# esp8266_relay.net
KiCad netlist of a schematic drawn in Altium Designer
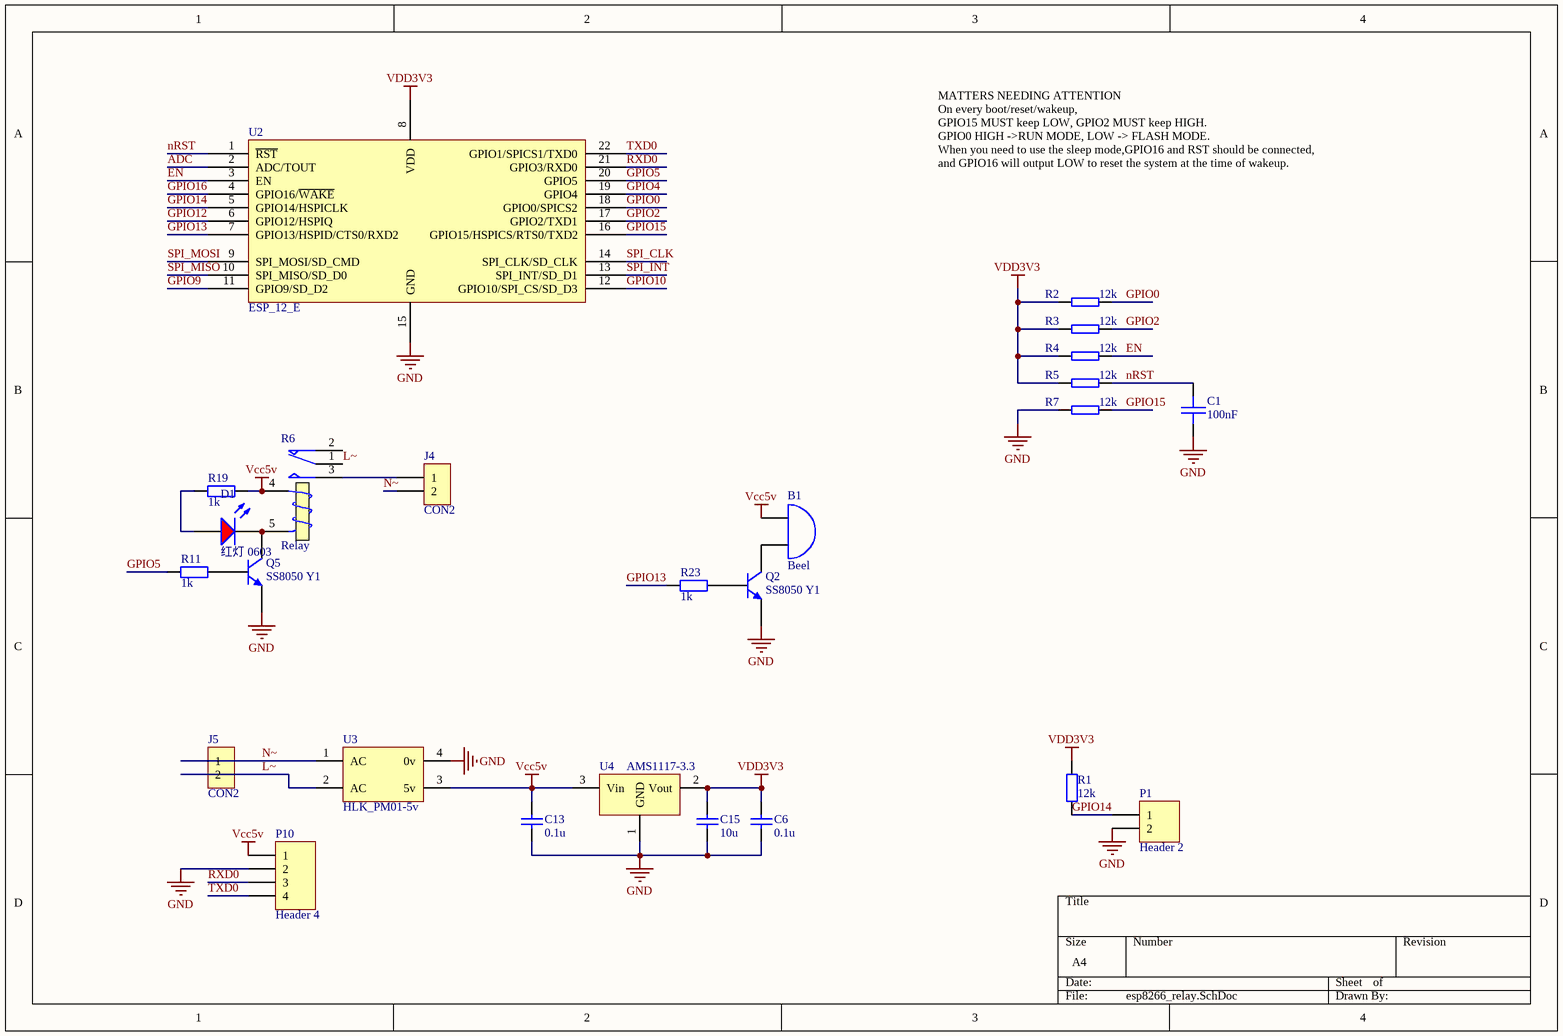
[diagram p0: esp8266_relay.SchDoc]

(export (version "E")
  (design (tool "Eeschema 10.0.6"))
  (components
    (comp (ref "B1") (value "Beel") (footprint "BEEL") (libsource (lib "元件库") (part "Beel")))
    (comp (ref "C1")
      (value "100nF")
      (footprint "C0603")
      (description "Surface mount capacitor 0402")
      (libsource (lib "Vowstar_Basic_Device") (part "SMT_C_0402"))
    )
    (comp (ref "C6") (value "0.1u") (footprint "C0603") (libsource (lib "元件库") (part "Cap_0402")))
    (comp (ref "C13") (value "0.1u") (footprint "C0603") (libsource (lib "元件库") (part "Cap_0402")))
    (comp (ref "C15") (value "10u") (footprint "C0603") (libsource (lib "元件库") (part "Cap_0402")))
    (comp (ref "D1")
      (value "红灯 0603")
      (footprint "0603_LED_S1")
      (description "发光二极管")
      (libsource (lib "Miscellaneous Devices LC") (part "0603 红灯"))
    )
    (comp (ref "J4")
      (value "CON2")
      (footprint "CON_5.08_2")
      (description "Connector")
      (libsource (lib "Miscellaneous Devices") (part "CON2"))
    )
    (comp (ref "J5")
      (value "CON2")
      (footprint "CON_5.08_2")
      (description "Connector")
      (libsource (lib "Miscellaneous Devices") (part "CON2"))
    )
    (comp (ref "P1")
      (value "Header 2")
      (footprint "HDR1X2")
      (description "Header, 2-Pin")
      (fields (field (name "PUBLISHER") "Altium Limited"))
      (libsource (lib "Miscellaneous Connectors") (part "Header 2"))
    )
    (comp (ref "P10")
      (value "Header 4")
      (footprint "HDR1X4")
      (description "Header, 4-Pin")
      (fields (field (name "PUBLISHER") "Altium Limited"))
      (libsource (lib "Miscellaneous Connectors") (part "Header 4"))
    )
    (comp (ref "Q2")
      (value "SS8050 Y1")
      (footprint "SOT-23(SOT-23-3)")
      (description "三极管")
      (libsource (lib "Miscellaneous Devices LC") (part "SOT-23 SS8050 Y1"))
    )
    (comp (ref "Q5")
      (value "SS8050 Y1")
      (footprint "SOT-23(SOT-23-3)")
      (description "三极管")
      (libsource (lib "Miscellaneous Devices LC") (part "SOT-23 SS8050 Y1"))
    )
    (comp (ref "R1") (value "12k") (footprint "Res_0603") (libsource (lib "元件库") (part "Res_0603")))
    (comp (ref "R2")
      (value "12k")
      (footprint "R0603")
      (description "Surface mount resistor 0402")
      (libsource (lib "Vowstar_Basic_Device") (part "SMT_R_0402"))
    )
    (comp (ref "R3")
      (value "12k")
      (footprint "R0603")
      (description "Surface mount resistor 0402")
      (libsource (lib "Vowstar_Basic_Device") (part "SMT_R_0402"))
    )
    (comp (ref "R4")
      (value "12k")
      (footprint "R0603")
      (description "Surface mount resistor 0402")
      (libsource (lib "Vowstar_Basic_Device") (part "SMT_R_0402"))
    )
    (comp (ref "R5")
      (value "12k")
      (footprint "R0603")
      (description "Surface mount resistor 0402")
      (libsource (lib "Vowstar_Basic_Device") (part "SMT_R_0402"))
    )
    (comp (ref "R6") (value "Relay") (footprint "HF3FF-JQC-3FF-005") (libsource (lib "元件库") (part "Relay")))
    (comp (ref "R7")
      (value "12k")
      (footprint "R0603")
      (description "Surface mount resistor 0402")
      (libsource (lib "Vowstar_Basic_Device") (part "SMT_R_0402"))
    )
    (comp (ref "R11") (value "1k") (footprint "R0603") (libsource (lib "元件库") (part "Res_0402")))
    (comp (ref "R19") (value "1k") (footprint "R0603") (libsource (lib "元件库") (part "Res_0402")))
    (comp (ref "R23") (value "1k") (footprint "R0603") (libsource (lib "") (part "Res_0402_1")))
    (comp (ref "U2")
      (value "ESP_12_E")
      (footprint "ESP8266")
      (description "ESP-12 Wi-Fi Module by AI-Thinker")
      (libsource (lib "Vowstar_Module") (part "ESP_12_E"))
    )
    (comp (ref "U3")
      (value "HLK_PM01-5v")
      (footprint "HLK_PM01-5v")
      (libsource (lib "mySchlib") (part "HLK_PM01-5v"))
    )
    (comp (ref "U4") (value "AMS1117-3.3") (footprint "AMS1117") (libsource (lib "元件库") (part "AMS1117")))
  )
  (nets
    (net (code "1") (name "/ADC") (class "Default")
      (node (ref "U2") (pin "2") (pinfunction "ADC/TOUT_2") (pintype "passive"))
    )
    (net (code "2") (name "/EN") (class "Default")
      (node (ref "R4") (pin "2") (pinfunction "2_2") (pintype "passive"))
      (node (ref "U2") (pin "3") (pinfunction "EN_3") (pintype "passive"))
    )
    (net (code "3") (name "/GPIO0") (class "Default")
      (node (ref "R2") (pin "2") (pinfunction "2_2") (pintype "passive"))
      (node (ref "U2") (pin "18") (pinfunction "GPIO0/SPICS2_18") (pintype "passive"))
    )
    (net (code "4") (name "/GPIO2") (class "Default")
      (node (ref "R3") (pin "2") (pinfunction "2_2") (pintype "passive"))
      (node (ref "U2") (pin "17") (pinfunction "GPIO2/TXD1_17") (pintype "passive"))
    )
    (net (code "5") (name "/GPIO4") (class "Default")
      (node (ref "U2") (pin "19") (pinfunction "GPIO4_19") (pintype "passive"))
    )
    (net (code "6") (name "/GPIO5") (class "Default")
      (node (ref "R11") (pin "1") (pinfunction "1_1") (pintype "passive"))
      (node (ref "U2") (pin "20") (pinfunction "GPIO5_20") (pintype "passive"))
    )
    (net (code "7") (name "/GPIO9") (class "Default")
      (node (ref "U2") (pin "11") (pinfunction "GPIO9/SD_D2_11") (pintype "passive"))
    )
    (net (code "8") (name "/GPIO10") (class "Default")
      (node (ref "U2") (pin "12") (pinfunction "GPIO10/SPI_CS/SD_D3_12") (pintype "passive"))
    )
    (net (code "9") (name "/GPIO12") (class "Default")
      (node (ref "U2") (pin "6") (pinfunction "GPIO12/HSPIQ_6") (pintype "passive"))
    )
    (net (code "10") (name "/GPIO13") (class "Default")
      (node (ref "R23") (pin "2") (pinfunction "2_2") (pintype "passive"))
      (node (ref "U2") (pin "7") (pinfunction "GPIO13/HSPID/CTS0/RXD2_7") (pintype "passive"))
    )
    (net (code "11") (name "/GPIO14") (class "Default")
      (node (ref "P1") (pin "1") (pinfunction "1_1") (pintype "passive"))
      (node (ref "R1") (pin "1") (pinfunction "1_1") (pintype "passive"))
      (node (ref "U2") (pin "5") (pinfunction "GPIO14/HSPICLK_5") (pintype "passive"))
    )
    (net (code "12") (name "/GPIO15") (class "Default")
      (node (ref "R7") (pin "2") (pinfunction "2_2") (pintype "passive"))
      (node (ref "U2") (pin "16") (pinfunction "GPIO15/HSPICS/RTS0/TXD2_16") (pintype "passive"))
    )
    (net (code "13") (name "/GPIO16") (class "Default")
      (node (ref "U2") (pin "4") (pinfunction "GPIO16/~{WAKE}_4") (pintype "passive"))
    )
    (net (code "14") (name "/L~") (class "Default")
      (node (ref "J5") (pin "2") (pinfunction "2_2") (pintype "passive"))
      (node (ref "R6") (pin "1") (pinfunction "COM_1") (pintype "passive"))
      (node (ref "U3") (pin "2") (pinfunction "AC_2") (pintype "passive"))
    )
    (net (code "15") (name "/N~") (class "Default")
      (node (ref "J4") (pin "2") (pinfunction "2_2") (pintype "passive"))
      (node (ref "J5") (pin "1") (pinfunction "1_1") (pintype "passive"))
      (node (ref "U3") (pin "1") (pinfunction "AC_1") (pintype "passive"))
    )
    (net (code "16") (name "/RXD0") (class "Default")
      (node (ref "P10") (pin "3") (pinfunction "3_3") (pintype "passive"))
      (node (ref "U2") (pin "21") (pinfunction "GPIO3/RXD0_21") (pintype "passive"))
    )
    (net (code "17") (name "/SPI_CLK") (class "Default")
      (node (ref "U2") (pin "14") (pinfunction "SPI_CLK/SD_CLK_14") (pintype "passive"))
    )
    (net (code "18") (name "/SPI_INT") (class "Default")
      (node (ref "U2") (pin "13") (pinfunction "SPI_INT/SD_D1_13") (pintype "passive"))
    )
    (net (code "19") (name "/SPI_MISO") (class "Default")
      (node (ref "U2") (pin "10") (pinfunction "SPI_MISO/SD_D0_10") (pintype "passive"))
    )
    (net (code "20") (name "/SPI_MOSI") (class "Default")
      (node (ref "U2") (pin "9") (pinfunction "SPI_MOSI/SD_CMD_9") (pintype "passive"))
    )
    (net (code "21") (name "/TXD0") (class "Default")
      (node (ref "P10") (pin "4") (pinfunction "4_4") (pintype "passive"))
      (node (ref "U2") (pin "22") (pinfunction "GPIO1/SPICS1/TXD0_22") (pintype "passive"))
    )
    (net (code "22") (name "/nRST") (class "Default")
      (node (ref "C1") (pin "1") (pinfunction "1_1") (pintype "passive"))
      (node (ref "R5") (pin "2") (pinfunction "2_2") (pintype "passive"))
      (node (ref "U2") (pin "1") (pinfunction "~{RST}_1") (pintype "passive"))
    )
    (net (code "23") (name "GND") (class "Default")
      (node (ref "C1") (pin "2") (pinfunction "2_2") (pintype "passive"))
      (node (ref "C13") (pin "1") (pinfunction "1_1") (pintype "passive"))
      (node (ref "C15") (pin "1") (pinfunction "1_1") (pintype "passive"))
      (node (ref "C6") (pin "1") (pinfunction "1_1") (pintype "passive"))
      (node (ref "P1") (pin "2") (pinfunction "2_2") (pintype "passive"))
      (node (ref "P10") (pin "2") (pinfunction "2_2") (pintype "passive"))
      (node (ref "Q2") (pin "2") (pinfunction "E_2") (pintype "passive"))
      (node (ref "Q5") (pin "2") (pinfunction "E_2") (pintype "passive"))
      (node (ref "R7") (pin "1") (pinfunction "1_1") (pintype "passive"))
      (node (ref "U2") (pin "15") (pinfunction "GND_15") (pintype "passive"))
      (node (ref "U3") (pin "4") (pinfunction "0v_4") (pintype "passive"))
      (node (ref "U4") (pin "1") (pinfunction "GND_1") (pintype "passive"))
    )
    (net (code "24") (name "Net-(B1-B)") (class "Default")
      (node (ref "B1") (pin "2") (pinfunction "B_2") (pintype "passive"))
      (node (ref "Q2") (pin "3") (pinfunction "C_3") (pintype "passive"))
    )
    (net (code "25") (name "Net-(D1-PadA)") (class "Default")
      (node (ref "D1") (pin "A") (pinfunction "A_A") (pintype "passive"))
      (node (ref "R19") (pin "1") (pinfunction "1_1") (pintype "passive"))
    )
    (net (code "26") (name "Net-(Q2-B)") (class "Default")
      (node (ref "Q2") (pin "1") (pinfunction "B_1") (pintype "passive"))
      (node (ref "R23") (pin "1") (pinfunction "1_1") (pintype "passive"))
    )
    (net (code "27") (name "Net-(Q5-B)") (class "Default")
      (node (ref "Q5") (pin "1") (pinfunction "B_1") (pintype "passive"))
      (node (ref "R11") (pin "2") (pinfunction "2_2") (pintype "passive"))
    )
    (net (code "28") (name "Net-(Q5-C)") (class "Default")
      (node (ref "D1") (pin "K") (pinfunction "K_K") (pintype "passive"))
      (node (ref "Q5") (pin "3") (pinfunction "C_3") (pintype "passive"))
      (node (ref "R6") (pin "5") (pinfunction "T2_5") (pintype "passive"))
    )
    (net (code "29") (name "Net-(R6-NO)") (class "Default")
      (node (ref "J4") (pin "1") (pinfunction "1_1") (pintype "passive"))
      (node (ref "R6") (pin "3") (pinfunction "NO_3") (pintype "passive"))
    )
    (net (code "30") (name "VDD3V3") (class "Default")
      (node (ref "C15") (pin "2") (pinfunction "2_2") (pintype "passive"))
      (node (ref "C6") (pin "2") (pinfunction "2_2") (pintype "passive"))
      (node (ref "R1") (pin "2") (pinfunction "2_2") (pintype "passive"))
      (node (ref "R2") (pin "1") (pinfunction "1_1") (pintype "passive"))
      (node (ref "R3") (pin "1") (pinfunction "1_1") (pintype "passive"))
      (node (ref "R4") (pin "1") (pinfunction "1_1") (pintype "passive"))
      (node (ref "R5") (pin "1") (pinfunction "1_1") (pintype "passive"))
      (node (ref "U2") (pin "8") (pinfunction "VDD_8") (pintype "passive"))
      (node (ref "U4") (pin "2") (pinfunction "Vout_2") (pintype "passive"))
    )
    (net (code "31") (name "Vcc5v") (class "Default")
      (node (ref "B1") (pin "1") (pinfunction "A_1") (pintype "passive"))
      (node (ref "C13") (pin "2") (pinfunction "2_2") (pintype "passive"))
      (node (ref "P10") (pin "1") (pinfunction "1_1") (pintype "passive"))
      (node (ref "R19") (pin "2") (pinfunction "2_2") (pintype "passive"))
      (node (ref "R6") (pin "4") (pinfunction "T1_4") (pintype "passive"))
      (node (ref "U3") (pin "3") (pinfunction "5v_3") (pintype "passive"))
      (node (ref "U4") (pin "3") (pinfunction "Vin_3") (pintype "passive"))
    )
    (net (code "32") (name "unconnected-(R6-NC-Pad2)") (class "Default")
      (node (ref "R6") (pin "2") (pinfunction "NC_2") (pintype "passive"))
    )
  )
)
